# STM32_POWER.net
KiCad netlist of a schematic drawn in Altium Designer
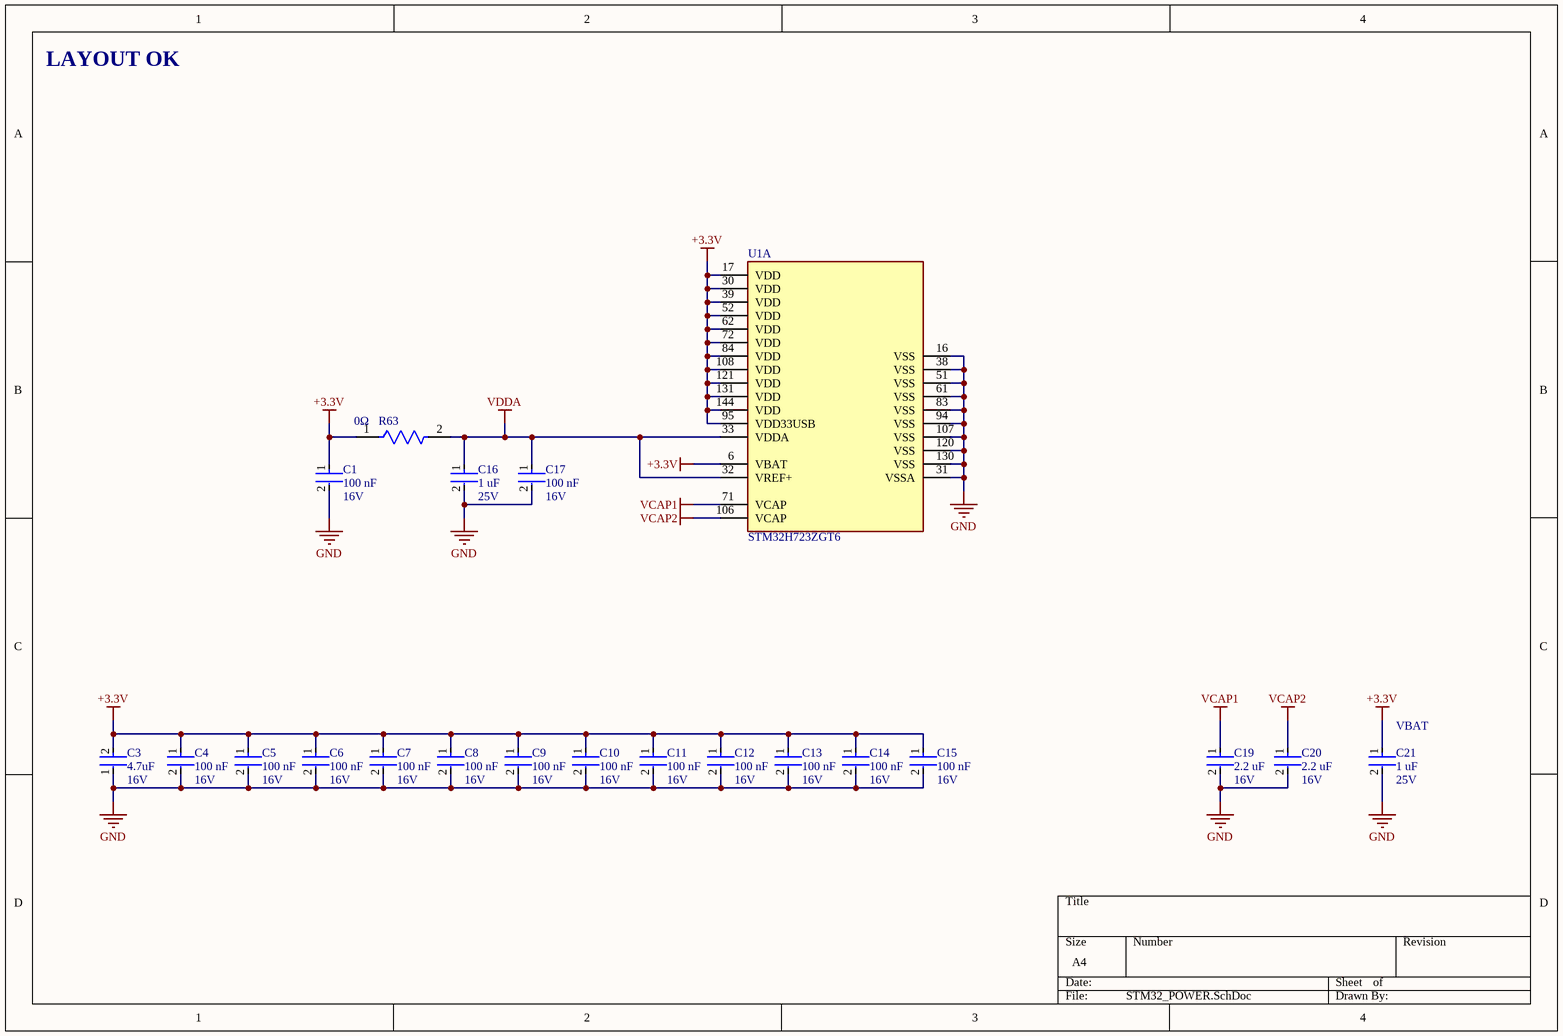
[diagram p0: STM32_POWER.SchDoc]

(export (version "E")
  (design (tool "Eeschema 10.0.6"))
  (components
    (comp (ref "C1")
      (value "CL05B104KO5VPNC")
      (footprint "FP-CL752-IPC_B")
      (description "Cap Ceramic 100nF 16V X7R ±10% SMD 0402 +125°C Paper T/R")
      (fields
        (field (name "CAPACITANCE") "100 nF")
        (field (name "VOLTAGE RATING") "16V")
        (field (name "TOLERANCE") "10%")
      )
      (libsource (lib "Altium Content Vault") (part "b4654b650e69147ec39a6b967a45e02"))
    )
    (comp (ref "C3")
      (value "C1608X5R1C475K080AC")
      (footprint "FP-C1608-080-0_1-IPC_B")
      (description "Multilayer Ceramic Capacitors 4.7μF ±10% 16V X5R SMD 0603")
      (fields
        (field (name "TOLERANCE") "10%")
        (field (name "VOLTAGE") "16V")
        (field (name "CAPACITANCE") "4.7uF")
      )
      (libsource (lib "Altium Content Vault") (part "236180d848d6139a670b325ea6854c9"))
    )
    (comp (ref "C4")
      (value "CL05B104KO5VPNC")
      (footprint "FP-CL752-IPC_B")
      (description "Cap Ceramic 100nF 16V X7R ±10% SMD 0402 +125°C Paper T/R")
      (fields
        (field (name "CAPACITANCE") "100 nF")
        (field (name "VOLTAGE RATING") "16V")
        (field (name "TOLERANCE") "10%")
      )
      (libsource (lib "Altium Content Vault") (part "b4654b650e69147ec39a6b967a45e02"))
    )
    (comp (ref "C5")
      (value "CL05B104KO5VPNC")
      (footprint "FP-CL752-IPC_B")
      (description "Cap Ceramic 100nF 16V X7R ±10% SMD 0402 +125°C Paper T/R")
      (fields
        (field (name "CAPACITANCE") "100 nF")
        (field (name "VOLTAGE RATING") "16V")
        (field (name "TOLERANCE") "10%")
      )
      (libsource (lib "Altium Content Vault") (part "b4654b650e69147ec39a6b967a45e02"))
    )
    (comp (ref "C6")
      (value "CL05B104KO5VPNC")
      (footprint "FP-CL752-IPC_B")
      (description "Cap Ceramic 100nF 16V X7R ±10% SMD 0402 +125°C Paper T/R")
      (fields
        (field (name "CAPACITANCE") "100 nF")
        (field (name "VOLTAGE RATING") "16V")
        (field (name "TOLERANCE") "10%")
      )
      (libsource (lib "Altium Content Vault") (part "b4654b650e69147ec39a6b967a45e02"))
    )
    (comp (ref "C7")
      (value "CL05B104KO5VPNC")
      (footprint "FP-CL752-IPC_B")
      (description "Cap Ceramic 100nF 16V X7R ±10% SMD 0402 +125°C Paper T/R")
      (fields
        (field (name "CAPACITANCE") "100 nF")
        (field (name "VOLTAGE RATING") "16V")
        (field (name "TOLERANCE") "10%")
      )
      (libsource (lib "Altium Content Vault") (part "b4654b650e69147ec39a6b967a45e02"))
    )
    (comp (ref "C8")
      (value "CL05B104KO5VPNC")
      (footprint "FP-CL752-IPC_B")
      (description "Cap Ceramic 100nF 16V X7R ±10% SMD 0402 +125°C Paper T/R")
      (fields
        (field (name "CAPACITANCE") "100 nF")
        (field (name "VOLTAGE RATING") "16V")
        (field (name "TOLERANCE") "10%")
      )
      (libsource (lib "Altium Content Vault") (part "b4654b650e69147ec39a6b967a45e02"))
    )
    (comp (ref "C9")
      (value "CL05B104KO5VPNC")
      (footprint "FP-CL752-IPC_B")
      (description "Cap Ceramic 100nF 16V X7R ±10% SMD 0402 +125°C Paper T/R")
      (fields
        (field (name "CAPACITANCE") "100 nF")
        (field (name "VOLTAGE RATING") "16V")
        (field (name "TOLERANCE") "10%")
      )
      (libsource (lib "Altium Content Vault") (part "b4654b650e69147ec39a6b967a45e02"))
    )
    (comp (ref "C10")
      (value "CL05B104KO5VPNC")
      (footprint "FP-CL752-IPC_B")
      (description "Cap Ceramic 100nF 16V X7R ±10% SMD 0402 +125°C Paper T/R")
      (fields
        (field (name "CAPACITANCE") "100 nF")
        (field (name "VOLTAGE RATING") "16V")
        (field (name "TOLERANCE") "10%")
      )
      (libsource (lib "Altium Content Vault") (part "b4654b650e69147ec39a6b967a45e02"))
    )
    (comp (ref "C11")
      (value "CL05B104KO5VPNC")
      (footprint "FP-CL752-IPC_B")
      (description "Cap Ceramic 100nF 16V X7R ±10% SMD 0402 +125°C Paper T/R")
      (fields
        (field (name "CAPACITANCE") "100 nF")
        (field (name "VOLTAGE RATING") "16V")
        (field (name "TOLERANCE") "10%")
      )
      (libsource (lib "Altium Content Vault") (part "b4654b650e69147ec39a6b967a45e02"))
    )
    (comp (ref "C12")
      (value "CL05B104KO5VPNC")
      (footprint "FP-CL752-IPC_B")
      (description "Cap Ceramic 100nF 16V X7R ±10% SMD 0402 +125°C Paper T/R")
      (fields
        (field (name "CAPACITANCE") "100 nF")
        (field (name "VOLTAGE RATING") "16V")
        (field (name "TOLERANCE") "10%")
      )
      (libsource (lib "Altium Content Vault") (part "b4654b650e69147ec39a6b967a45e02"))
    )
    (comp (ref "C13")
      (value "CL05B104KO5VPNC")
      (footprint "FP-CL752-IPC_B")
      (description "Cap Ceramic 100nF 16V X7R ±10% SMD 0402 +125°C Paper T/R")
      (fields
        (field (name "CAPACITANCE") "100 nF")
        (field (name "VOLTAGE RATING") "16V")
        (field (name "TOLERANCE") "10%")
      )
      (libsource (lib "Altium Content Vault") (part "b4654b650e69147ec39a6b967a45e02"))
    )
    (comp (ref "C14")
      (value "CL05B104KO5VPNC")
      (footprint "FP-CL752-IPC_B")
      (description "Cap Ceramic 100nF 16V X7R ±10% SMD 0402 +125°C Paper T/R")
      (fields
        (field (name "CAPACITANCE") "100 nF")
        (field (name "VOLTAGE RATING") "16V")
        (field (name "TOLERANCE") "10%")
      )
      (libsource (lib "Altium Content Vault") (part "b4654b650e69147ec39a6b967a45e02"))
    )
    (comp (ref "C15")
      (value "CL05B104KO5VPNC")
      (footprint "FP-CL752-IPC_B")
      (description "Cap Ceramic 100nF 16V X7R ±10% SMD 0402 +125°C Paper T/R")
      (fields
        (field (name "CAPACITANCE") "100 nF")
        (field (name "VOLTAGE RATING") "16V")
        (field (name "TOLERANCE") "10%")
      )
      (libsource (lib "Altium Content Vault") (part "b4654b650e69147ec39a6b967a45e02"))
    )
    (comp (ref "C16")
      (value "GCM188R71E105KA64D")
      (footprint "FP-GCM188-0_1-IPC_B")
      (fields
        (field (name "TOLERANCE") "10%")
        (field (name "CAPACITANCE") "1 uF")
        (field (name "VOLTAGE RATING") "25V")
        (field (name "VOLTAGE") "25V")
      )
      (libsource (lib "Altium Content Vault") (part "02cd4be3c70576c341d710602a673aa"))
    )
    (comp (ref "C17")
      (value "CL05B104KO5VPNC")
      (footprint "FP-CL752-IPC_B")
      (description "Cap Ceramic 100nF 16V X7R ±10% SMD 0402 +125°C Paper T/R")
      (fields
        (field (name "CAPACITANCE") "100 nF")
        (field (name "VOLTAGE RATING") "16V")
        (field (name "TOLERANCE") "10%")
      )
      (libsource (lib "Altium Content Vault") (part "b4654b650e69147ec39a6b967a45e02"))
    )
    (comp (ref "C19")
      (value "CL10A225KO8NNNC")
      (footprint "FP-CL10-IPC_B")
      (description "Cap Ceramic 2.2uF 16V X5R ±10% Pad SMD 0603 +85°C T/R")
      (fields
        (field (name "CAPACITANCE") "2.2 uF")
        (field (name "VOLTAGE RATING") "16V")
        (field (name "TOLERANCE") "10%")
        (field (name "VOLTAGE") "16V")
      )
      (libsource (lib "Altium Content Vault") (part "b4654b650e69147ec39a6b967a45e02"))
    )
    (comp (ref "C20")
      (value "CL10A225KO8NNNC")
      (footprint "FP-CL10-IPC_B")
      (description "Cap Ceramic 2.2uF 16V X5R ±10% Pad SMD 0603 +85°C T/R")
      (fields
        (field (name "CAPACITANCE") "2.2 uF")
        (field (name "VOLTAGE RATING") "16V")
        (field (name "TOLERANCE") "10%")
        (field (name "VOLTAGE") "16V")
      )
      (libsource (lib "Altium Content Vault") (part "b4654b650e69147ec39a6b967a45e02"))
    )
    (comp (ref "C21")
      (value "GCM188R71E105KA64D")
      (footprint "FP-GCM188-0_1-IPC_B")
      (fields
        (field (name "TOLERANCE") "10%")
        (field (name "CAPACITANCE") "1 uF")
        (field (name "VOLTAGE RATING") "25V")
        (field (name "VOLTAGE") "25V")
      )
      (libsource (lib "Altium Content Vault") (part "02cd4be3c70576c341d710602a673aa"))
    )
    (comp (ref "R63")
      (value "CRCW06030000Z0EAHP")
      (footprint "FP-CRCW0603-HPe3-IPC_B")
      (description "RES Thick Film, 0Ω, , 0.33W, , 0603")
      (fields (field (name "RESISTANCE") "0Ω"))
      (libsource (lib "Altium Content Vault") (part "1029c3af85768c4190bb7ad29bc67b5"))
    )
    (comp (ref "U1")
      (value "STM32H723ZGT6")
      (footprint "CQFP50P2200X2200X160-144M")
      (description "RISC Microcontroller, 32-Bit, FLASH, CORTEX-M7 CPU, 550MHz, CMOS, PQFP144")
      (fields (field (name "MANUFACTURER") "STMicroelectronics"))
      (libsource (lib "STM32H723ZGT6") (part "STM32H723ZGT6"))
    )
  )
  (nets
    (net (code "1") (name "+3.3V") (class "Default")
      (node (ref "C1") (pin "1") (pinfunction "1_1") (pintype "passive"))
      (node (ref "C10") (pin "1") (pinfunction "1_1") (pintype "passive"))
      (node (ref "C11") (pin "1") (pinfunction "1_1") (pintype "passive"))
      (node (ref "C12") (pin "1") (pinfunction "1_1") (pintype "passive"))
      (node (ref "C13") (pin "1") (pinfunction "1_1") (pintype "passive"))
      (node (ref "C14") (pin "1") (pinfunction "1_1") (pintype "passive"))
      (node (ref "C15") (pin "1") (pinfunction "1_1") (pintype "passive"))
      (node (ref "C21") (pin "1") (pinfunction "1_1") (pintype "passive"))
      (node (ref "C3") (pin "2") (pinfunction "2_2") (pintype "passive"))
      (node (ref "C4") (pin "1") (pinfunction "1_1") (pintype "passive"))
      (node (ref "C5") (pin "1") (pinfunction "1_1") (pintype "passive"))
      (node (ref "C6") (pin "1") (pinfunction "1_1") (pintype "passive"))
      (node (ref "C7") (pin "1") (pinfunction "1_1") (pintype "passive"))
      (node (ref "C8") (pin "1") (pinfunction "1_1") (pintype "passive"))
      (node (ref "C9") (pin "1") (pinfunction "1_1") (pintype "passive"))
      (node (ref "R63") (pin "1") (pinfunction "1_1") (pintype "passive"))
      (node (ref "U1") (pin "108") (pinfunction "VDD_108") (pintype "power_in"))
      (node (ref "U1") (pin "121") (pinfunction "VDD_121") (pintype "power_in"))
      (node (ref "U1") (pin "131") (pinfunction "VDD_131") (pintype "power_in"))
      (node (ref "U1") (pin "144") (pinfunction "VDD_144") (pintype "power_in"))
      (node (ref "U1") (pin "17") (pinfunction "VDD_17") (pintype "power_in"))
      (node (ref "U1") (pin "30") (pinfunction "VDD_30") (pintype "power_in"))
      (node (ref "U1") (pin "39") (pinfunction "VDD_39") (pintype "power_in"))
      (node (ref "U1") (pin "52") (pinfunction "VDD_52") (pintype "power_in"))
      (node (ref "U1") (pin "6") (pinfunction "VBAT_6") (pintype "power_in"))
      (node (ref "U1") (pin "62") (pinfunction "VDD_62") (pintype "power_in"))
      (node (ref "U1") (pin "72") (pinfunction "VDD_72") (pintype "power_in"))
      (node (ref "U1") (pin "84") (pinfunction "VDD_84") (pintype "power_in"))
      (node (ref "U1") (pin "95") (pinfunction "VDD33USB_95") (pintype "power_in"))
    )
    (net (code "2") (name "GND") (class "Default")
      (node (ref "C1") (pin "2") (pinfunction "2_2") (pintype "passive"))
      (node (ref "C10") (pin "2") (pinfunction "2_2") (pintype "passive"))
      (node (ref "C11") (pin "2") (pinfunction "2_2") (pintype "passive"))
      (node (ref "C12") (pin "2") (pinfunction "2_2") (pintype "passive"))
      (node (ref "C13") (pin "2") (pinfunction "2_2") (pintype "passive"))
      (node (ref "C14") (pin "2") (pinfunction "2_2") (pintype "passive"))
      (node (ref "C15") (pin "2") (pinfunction "2_2") (pintype "passive"))
      (node (ref "C16") (pin "2") (pinfunction "2_2") (pintype "passive"))
      (node (ref "C17") (pin "2") (pinfunction "2_2") (pintype "passive"))
      (node (ref "C19") (pin "2") (pinfunction "2_2") (pintype "passive"))
      (node (ref "C20") (pin "2") (pinfunction "2_2") (pintype "passive"))
      (node (ref "C21") (pin "2") (pinfunction "2_2") (pintype "passive"))
      (node (ref "C3") (pin "1") (pinfunction "1_1") (pintype "passive"))
      (node (ref "C4") (pin "2") (pinfunction "2_2") (pintype "passive"))
      (node (ref "C5") (pin "2") (pinfunction "2_2") (pintype "passive"))
      (node (ref "C6") (pin "2") (pinfunction "2_2") (pintype "passive"))
      (node (ref "C7") (pin "2") (pinfunction "2_2") (pintype "passive"))
      (node (ref "C8") (pin "2") (pinfunction "2_2") (pintype "passive"))
      (node (ref "C9") (pin "2") (pinfunction "2_2") (pintype "passive"))
      (node (ref "U1") (pin "107") (pinfunction "VSS_107") (pintype "power_in"))
      (node (ref "U1") (pin "120") (pinfunction "VSS_120") (pintype "power_in"))
      (node (ref "U1") (pin "130") (pinfunction "VSS_130") (pintype "power_in"))
      (node (ref "U1") (pin "16") (pinfunction "VSS_16") (pintype "power_in"))
      (node (ref "U1") (pin "31") (pinfunction "VSSA_31") (pintype "power_in"))
      (node (ref "U1") (pin "38") (pinfunction "VSS_38") (pintype "power_in"))
      (node (ref "U1") (pin "51") (pinfunction "VSS_51") (pintype "power_in"))
      (node (ref "U1") (pin "61") (pinfunction "VSS_61") (pintype "power_in"))
      (node (ref "U1") (pin "83") (pinfunction "VSS_83") (pintype "power_in"))
      (node (ref "U1") (pin "94") (pinfunction "VSS_94") (pintype "power_in"))
    )
    (net (code "3") (name "VCAP1") (class "Default")
      (node (ref "C19") (pin "1") (pinfunction "1_1") (pintype "passive"))
      (node (ref "U1") (pin "71") (pinfunction "VCAP_71") (pintype "power_in"))
    )
    (net (code "4") (name "VCAP2") (class "Default")
      (node (ref "C20") (pin "1") (pinfunction "1_1") (pintype "passive"))
      (node (ref "U1") (pin "106") (pinfunction "VCAP_106") (pintype "power_in"))
    )
    (net (code "5") (name "VDDA") (class "Default")
      (node (ref "C16") (pin "1") (pinfunction "1_1") (pintype "passive"))
      (node (ref "C17") (pin "1") (pinfunction "1_1") (pintype "passive"))
      (node (ref "R63") (pin "2") (pinfunction "2_2") (pintype "passive"))
      (node (ref "U1") (pin "32") (pinfunction "VREF+_32") (pintype "power_in"))
      (node (ref "U1") (pin "33") (pinfunction "VDDA_33") (pintype "power_in"))
    )
  )
)
